# Ampli50g.net
KiCad netlist of a schematic drawn in Altium Designer
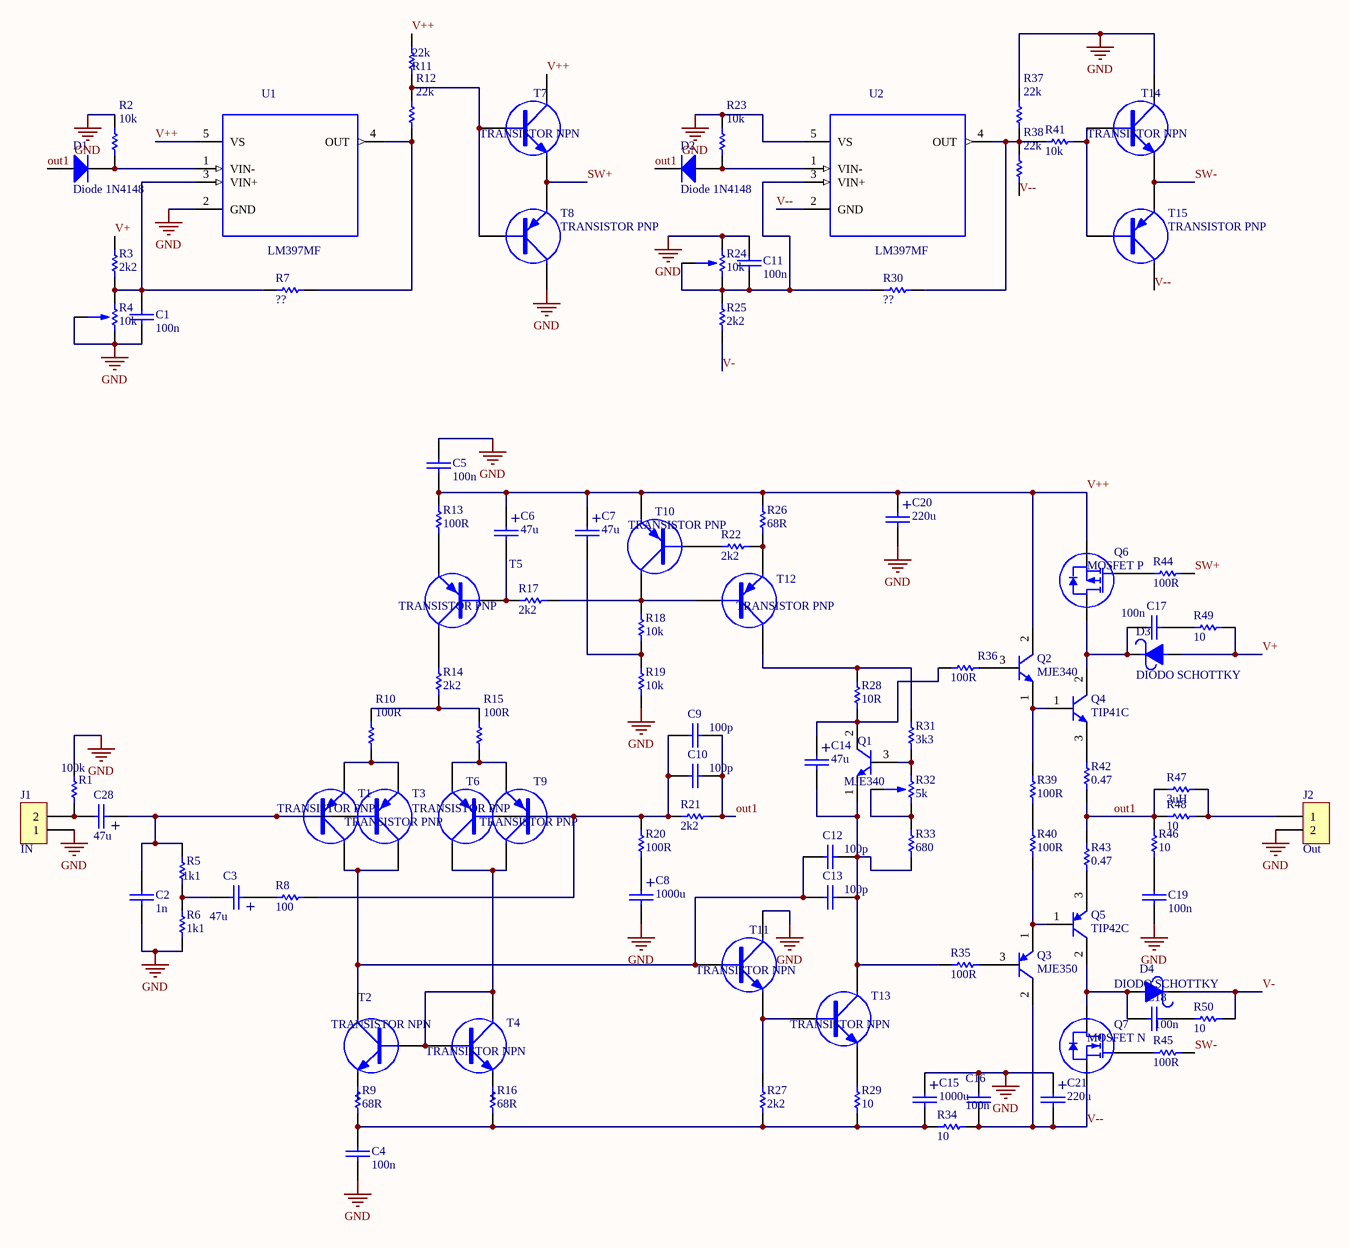
[diagram p0: Ampli50g.SchDoc]

(export (version "E")
  (design (tool "Eeschema 10.0.6"))
  (components
    (comp (ref "C1") (value "100n") (footprint "0805") (libsource (lib "LIBEBAL") (part "CAP")))
    (comp (ref "C2") (value "1n") (footprint "CAP200") (libsource (lib "LIBEBAL") (part "CAP")))
    (comp (ref "C3") (value "47u") (footprint "CAP100RP") (libsource (lib "LIBEBAL") (part "CAPPOL")))
    (comp (ref "C4") (value "100n") (footprint "CAP200") (libsource (lib "LIBEBAL") (part "CAP")))
    (comp (ref "C5") (value "100n") (footprint "CAP200") (libsource (lib "LIBEBAL") (part "CAP")))
    (comp (ref "C6") (value "47u") (footprint "CAP100RP") (libsource (lib "LIBEBAL") (part "CAPPOL")))
    (comp (ref "C7") (value "47u") (footprint "CAP100RP") (libsource (lib "LIBEBAL") (part "CAPPOL")))
    (comp (ref "C8") (value "1000u") (footprint "CAP200RP2") (libsource (lib "LIBEBAL") (part "CAPPOL")))
    (comp (ref "C9") (value "100p") (footprint "0805") (libsource (lib "LIBEBAL") (part "CAP")))
    (comp (ref "C10") (value "100p") (footprint "0805") (libsource (lib "LIBEBAL") (part "CAP")))
    (comp (ref "C11") (value "100n") (footprint "0805") (libsource (lib "LIBEBAL") (part "CAP")))
    (comp (ref "C12") (value "100p") (footprint "0805") (libsource (lib "LIBEBAL") (part "CAP")))
    (comp (ref "C13") (value "100p") (footprint "0805") (libsource (lib "LIBEBAL") (part "CAP")))
    (comp (ref "C14") (value "47u") (footprint "CAP100RP") (libsource (lib "LIBEBAL") (part "CAPPOL")))
    (comp (ref "C15") (value "1000u") (footprint "CAP200RP2") (libsource (lib "LIBEBAL") (part "CAPPOL")))
    (comp (ref "C16") (value "100n") (footprint "CAP200") (libsource (lib "LIBEBAL") (part "CAP")))
    (comp (ref "C17") (value "100n") (footprint "CAP200") (libsource (lib "LIBEBAL") (part "CAP")))
    (comp (ref "C18") (value "100n") (footprint "CAP200") (libsource (lib "LIBEBAL") (part "CAP")))
    (comp (ref "C19") (value "100n") (footprint "CAP200") (libsource (lib "LIBEBAL") (part "CAP")))
    (comp (ref "C20") (value "220u") (footprint "CAP200RP2") (libsource (lib "LIBEBAL") (part "CAPPOL")))
    (comp (ref "C21") (value "220u") (footprint "CAP200RP2") (libsource (lib "LIBEBAL") (part "CAPPOL")))
    (comp (ref "C28") (value "47u") (footprint "CAP100RP") (libsource (lib "LIBEBAL") (part "CAPPOL")))
    (comp (ref "D1")
      (value "Diode 1N4148")
      (footprint "DO-35")
      (description "High Conductance Fast Diode")
      (fields (field (name "PUBLISHER") "Altium Limited"))
      (libsource (lib "Miscellaneous Devices") (part "Diode 1N4148"))
    )
    (comp (ref "D2")
      (value "Diode 1N4148")
      (footprint "DO-35")
      (description "High Conductance Fast Diode")
      (fields (field (name "PUBLISHER") "Altium Limited"))
      (libsource (lib "Miscellaneous Devices") (part "Diode 1N4148"))
    )
    (comp (ref "D3")
      (value "DIODO SCHOTTKY")
      (footprint "SMCK")
      (libsource (lib "LIBEBAL") (part "DIODO SCHOTTKY"))
    )
    (comp (ref "D4")
      (value "DIODO SCHOTTKY")
      (footprint "SMCK")
      (libsource (lib "LIBEBAL") (part "DIODO SCHOTTKY"))
    )
    (comp (ref "J1") (value "IN") (footprint "BORNERA2") (libsource (lib "LIBEBAL") (part "BORNERA 2")))
    (comp (ref "J2") (value "Out") (footprint "BORNERA2") (libsource (lib "") (part "BORNERA 2_1")))
    (comp (ref "Q1")
      (value "MJE340")
      (footprint "ONSC-TO-225-3-77-09")
      (description "Plastic Medium-Power NPN Silicon Transistor, 3-Pin TO-225, Bulk Box")
      (fields (field (name "MANUFACTURER") "On Semiconductor"))
      (libsource (lib "ON Semi General Purpose Transistors") (part "MJE340"))
    )
    (comp (ref "Q2")
      (value "MJE340")
      (footprint "ONSC-TO-225-3-77-09")
      (description "Plastic Medium-Power NPN Silicon Transistor, 3-Pin TO-225, Bulk Box")
      (fields (field (name "MANUFACTURER") "On Semiconductor"))
      (libsource (lib "ON Semi General Purpose Transistors") (part "MJE340"))
    )
    (comp (ref "Q3")
      (value "MJE350")
      (footprint "ONSC-TO-225-3-77-09")
      (description "Plastic Medium-Power PNP Silicon Transistor, 3-Pin TO-225, Bulk Box")
      (fields (field (name "MANUFACTURER") "On Semiconductor"))
      (libsource (lib "ON Semi General Purpose Transistors") (part "MJE350"))
    )
    (comp (ref "Q4")
      (value "TIP41C")
      (footprint "ONSC-TO-220-3-221A-09")
      (description "Complementary Silicon Plastic Power Transistor, 3-Pin TO-220, Tube")
      (fields (field (name "MANUFACTURER") "On Semiconductor"))
      (libsource (lib "ON Semi General Purpose Transistors") (part "TIP41C"))
    )
    (comp (ref "Q5")
      (value "TIP42C")
      (footprint "ONSC-TO-220-3-221A-09")
      (description "Complementary Silicon Plastic Power Transistor, 3-Pin TO-220, Tube")
      (fields (field (name "MANUFACTURER") "On Semiconductor"))
      (libsource (lib "ON Semi General Purpose Transistors") (part "TIP42C"))
    )
    (comp (ref "Q6") (value "MOSFET P") (footprint "TO-220 V") (libsource (lib "LIBEBAL") (part "MOSFET P")))
    (comp (ref "Q7") (value "MOSFET N") (footprint "TO-220 V") (libsource (lib "LIBEBAL") (part "MOSFET N")))
    (comp (ref "R1") (value "100k") (footprint "RES400") (libsource (lib "LIBEBAL") (part "RES")))
    (comp (ref "R2") (value "10k") (footprint "1206") (libsource (lib "LIBEBAL") (part "RES")))
    (comp (ref "R3") (value "2k2") (footprint "RES400") (libsource (lib "LIBEBAL") (part "RES")))
    (comp (ref "R4") (value "10k") (footprint "PRESET V") (libsource (lib "LIBEBAL") (part "PRESET")))
    (comp (ref "R5") (value "1k1") (footprint "1206") (libsource (lib "LIBEBAL") (part "RES")))
    (comp (ref "R6") (value "1k1") (footprint "1206") (libsource (lib "LIBEBAL") (part "RES")))
    (comp (ref "R7")
      (value "??")
      (footprint "1206")
      (description "RES SMD 1/2W 1206")
      (libsource (lib "LIBEBAL") (part "RES"))
    )
    (comp (ref "R8") (value "100") (footprint "1206") (libsource (lib "LIBEBAL") (part "RES")))
    (comp (ref "R9") (value "68R") (footprint "1206") (libsource (lib "LIBEBAL") (part "RES")))
    (comp (ref "R10") (value "100R") (footprint "1206") (libsource (lib "LIBEBAL") (part "RES")))
    (comp (ref "R11")
      (value "22k")
      (footprint "1206")
      (description "RES SMD 1/2W 1206")
      (libsource (lib "LIBEBAL") (part "RES"))
    )
    (comp (ref "R12")
      (value "22k")
      (footprint "1206")
      (description "RES SMD 1/2W 1206")
      (libsource (lib "LIBEBAL") (part "RES"))
    )
    (comp (ref "R13") (value "100R") (footprint "1206") (libsource (lib "LIBEBAL") (part "RES")))
    (comp (ref "R14") (value "2k2") (footprint "1206") (libsource (lib "LIBEBAL") (part "RES")))
    (comp (ref "R15")
      (value "100R")
      (footprint "1206")
      (description "RES SMD 1/2W 1206")
      (libsource (lib "LIBEBAL") (part "RES"))
    )
    (comp (ref "R16") (value "68R") (footprint "1206") (libsource (lib "LIBEBAL") (part "RES")))
    (comp (ref "R17") (value "2k2") (footprint "1206") (libsource (lib "LIBEBAL") (part "RES")))
    (comp (ref "R18") (value "10k") (footprint "1206") (libsource (lib "LIBEBAL") (part "RES")))
    (comp (ref "R19") (value "10k") (footprint "1206") (libsource (lib "LIBEBAL") (part "RES")))
    (comp (ref "R20") (value "100R") (footprint "1206") (libsource (lib "LIBEBAL") (part "RES")))
    (comp (ref "R21") (value "2k2") (footprint "1206") (libsource (lib "LIBEBAL") (part "RES")))
    (comp (ref "R22") (value "2k2") (footprint "1206") (libsource (lib "LIBEBAL") (part "RES")))
    (comp (ref "R23") (value "10k") (footprint "1206") (libsource (lib "LIBEBAL") (part "RES")))
    (comp (ref "R24") (value "10k") (footprint "PRESET V") (libsource (lib "LIBEBAL") (part "PRESET")))
    (comp (ref "R25") (value "2k2") (footprint "RES400") (libsource (lib "LIBEBAL") (part "RES")))
    (comp (ref "R26") (value "68R") (footprint "1206") (libsource (lib "LIBEBAL") (part "RES")))
    (comp (ref "R27") (value "2k2") (footprint "1206") (libsource (lib "LIBEBAL") (part "RES")))
    (comp (ref "R28") (value "10R") (footprint "1206") (libsource (lib "LIBEBAL") (part "RES")))
    (comp (ref "R29") (value "10") (footprint "1206") (libsource (lib "LIBEBAL") (part "RES")))
    (comp (ref "R30")
      (value "??")
      (footprint "1206")
      (description "RES SMD 1/2W 1206")
      (libsource (lib "LIBEBAL") (part "RES"))
    )
    (comp (ref "R31") (value "3k3") (footprint "1206") (libsource (lib "LIBEBAL") (part "RES")))
    (comp (ref "R32") (value "5k") (footprint "PRESET V") (libsource (lib "LIBEBAL") (part "PRESET")))
    (comp (ref "R33") (value "680") (footprint "1206") (libsource (lib "LIBEBAL") (part "RES")))
    (comp (ref "R34") (value "10") (footprint "RES500") (libsource (lib "LIBEBAL") (part "RES")))
    (comp (ref "R35") (value "100R") (footprint "1206") (libsource (lib "LIBEBAL") (part "RES")))
    (comp (ref "R36") (value "100R") (footprint "1206") (libsource (lib "LIBEBAL") (part "RES")))
    (comp (ref "R37")
      (value "22k")
      (footprint "1206")
      (description "RES SMD 1/2W 1206")
      (libsource (lib "LIBEBAL") (part "RES"))
    )
    (comp (ref "R38")
      (value "22k")
      (footprint "1206")
      (description "RES SMD 1/2W 1206")
      (libsource (lib "LIBEBAL") (part "RES"))
    )
    (comp (ref "R39") (value "100R") (footprint "RES500") (libsource (lib "LIBEBAL") (part "RES")))
    (comp (ref "R40") (value "100R") (footprint "RES500") (libsource (lib "LIBEBAL") (part "RES")))
    (comp (ref "R41")
      (value "10k")
      (footprint "1206")
      (description "RES SMD 1/2W 1206")
      (libsource (lib "LIBEBAL") (part "RES"))
    )
    (comp (ref "R42") (value "0.47") (footprint "RES1200") (libsource (lib "LIBEBAL") (part "RES")))
    (comp (ref "R43") (value "0.47") (footprint "RES1200") (libsource (lib "LIBEBAL") (part "RES")))
    (comp (ref "R44") (value "100R") (footprint "1206") (libsource (lib "LIBEBAL") (part "RES")))
    (comp (ref "R45") (value "100R") (footprint "1206") (libsource (lib "LIBEBAL") (part "RES")))
    (comp (ref "R46") (value "10") (footprint "RES600") (libsource (lib "LIBEBAL") (part "RES")))
    (comp (ref "R47") (value "3uH") (footprint "RES600") (libsource (lib "LIBEBAL") (part "RES")))
    (comp (ref "R48") (value "10") (footprint "RES600") (libsource (lib "LIBEBAL") (part "RES")))
    (comp (ref "R49") (value "10") (footprint "1206") (libsource (lib "LIBEBAL") (part "RES")))
    (comp (ref "R50") (value "10") (footprint "1206") (libsource (lib "LIBEBAL") (part "RES")))
    (comp (ref "T1")
      (value "TRANSISTOR PNP")
      (footprint "SOT23")
      (libsource (lib "LIBEBAL") (part "TRANSISTOR PNP"))
    )
    (comp (ref "T2")
      (value "TRANSISTOR NPN")
      (footprint "SOT23")
      (libsource (lib "LIBEBAL") (part "TRANSISTOR NPN"))
    )
    (comp (ref "T3")
      (value "TRANSISTOR PNP")
      (footprint "SOT23")
      (libsource (lib "LIBEBAL") (part "TRANSISTOR PNP"))
    )
    (comp (ref "T4")
      (value "TRANSISTOR NPN")
      (footprint "SOT23")
      (libsource (lib "LIBEBAL") (part "TRANSISTOR NPN"))
    )
    (comp (ref "T5")
      (value "TRANSISTOR PNP")
      (footprint "SOT23")
      (libsource (lib "LIBEBAL") (part "TRANSISTOR PNP"))
    )
    (comp (ref "T6")
      (value "TRANSISTOR PNP")
      (footprint "SOT23")
      (libsource (lib "LIBEBAL") (part "TRANSISTOR PNP"))
    )
    (comp (ref "T7")
      (value "TRANSISTOR NPN")
      (footprint "SOT23")
      (libsource (lib "LIBEBAL") (part "TRANSISTOR NPN"))
    )
    (comp (ref "T8")
      (value "TRANSISTOR PNP")
      (footprint "SOT23")
      (libsource (lib "LIBEBAL") (part "TRANSISTOR PNP"))
    )
    (comp (ref "T9")
      (value "TRANSISTOR PNP")
      (footprint "SOT23")
      (libsource (lib "LIBEBAL") (part "TRANSISTOR PNP"))
    )
    (comp (ref "T10")
      (value "TRANSISTOR PNP")
      (footprint "SOT23")
      (libsource (lib "LIBEBAL") (part "TRANSISTOR PNP"))
    )
    (comp (ref "T11")
      (value "TRANSISTOR NPN")
      (footprint "SOT23")
      (libsource (lib "LIBEBAL") (part "TRANSISTOR NPN"))
    )
    (comp (ref "T12")
      (value "TRANSISTOR PNP")
      (footprint "SOT23")
      (libsource (lib "LIBEBAL") (part "TRANSISTOR PNP"))
    )
    (comp (ref "T13")
      (value "TRANSISTOR NPN")
      (footprint "SOT23")
      (libsource (lib "LIBEBAL") (part "TRANSISTOR NPN"))
    )
    (comp (ref "T14")
      (value "TRANSISTOR NPN")
      (footprint "SOT23")
      (libsource (lib "LIBEBAL") (part "TRANSISTOR NPN"))
    )
    (comp (ref "T15")
      (value "TRANSISTOR PNP")
      (footprint "SOT23")
      (libsource (lib "LIBEBAL") (part "TRANSISTOR PNP"))
    )
    (comp (ref "U1")
      (value "LM397MF")
      (footprint "SOT95P285X120-5N")
      (description "General Purpose Comparator, Single, 250ns, Sot23-5, Full Reel")
      (fields (field (name "MP") "LM397MF/NOPB") (field (name "MF") "Texas Instruments"))
      (libsource (lib "LM397MF") (part "LM397MF"))
    )
    (comp (ref "U2")
      (value "LM397MF")
      (footprint "SOT95P285X120-5N")
      (description "General Purpose Comparator, Single, 250ns, Sot23-5, Full Reel")
      (fields (field (name "MP") "LM397MF/NOPB") (field (name "MF") "Texas Instruments"))
      (libsource (lib "LM397MF") (part "LM397MF"))
    )
  )
  (nets
    (net (code "1") (name "/SW+") (class "Default")
      (node (ref "R44") (pin "1") (pinfunction "1_1") (pintype "passive"))
      (node (ref "T7") (pin "3") (pinfunction "E_3") (pintype "passive"))
      (node (ref "T8") (pin "3") (pinfunction "E_3") (pintype "passive"))
    )
    (net (code "2") (name "/SW-") (class "Default")
      (node (ref "R45") (pin "1") (pinfunction "1_1") (pintype "passive"))
      (node (ref "T14") (pin "3") (pinfunction "E_3") (pintype "passive"))
      (node (ref "T15") (pin "3") (pinfunction "E_3") (pintype "passive"))
    )
    (net (code "3") (name "/V+") (class "Default")
      (node (ref "D3") (pin "1") (pinfunction "1_1") (pintype "passive"))
      (node (ref "R3") (pin "2") (pinfunction "2_2") (pintype "passive"))
      (node (ref "R49") (pin "2") (pinfunction "2_2") (pintype "passive"))
    )
    (net (code "4") (name "/V++") (class "Default")
      (node (ref "C20") (pin "1") (pinfunction "1_1") (pintype "passive"))
      (node (ref "C5") (pin "2") (pinfunction "2_2") (pintype "passive"))
      (node (ref "C6") (pin "1") (pinfunction "1_1") (pintype "passive"))
      (node (ref "C7") (pin "1") (pinfunction "1_1") (pintype "passive"))
      (node (ref "Q2") (pin "2") (pinfunction "C_2") (pintype "passive"))
      (node (ref "Q6") (pin "3") (pinfunction "S_3") (pintype "passive"))
      (node (ref "R11") (pin "2") (pinfunction "2_2") (pintype "passive"))
      (node (ref "R13") (pin "2") (pinfunction "2_2") (pintype "passive"))
      (node (ref "R26") (pin "2") (pinfunction "2_2") (pintype "passive"))
      (node (ref "T10") (pin "3") (pinfunction "E_3") (pintype "passive"))
      (node (ref "T7") (pin "2") (pinfunction "C_2") (pintype "passive"))
      (node (ref "U1") (pin "5") (pinfunction "VS_5") (pintype "power_in"))
    )
    (net (code "5") (name "/V-") (class "Default")
      (node (ref "D4") (pin "2") (pinfunction "2_2") (pintype "passive"))
      (node (ref "R25") (pin "1") (pinfunction "1_1") (pintype "passive"))
      (node (ref "R50") (pin "2") (pinfunction "2_2") (pintype "passive"))
    )
    (net (code "6") (name "/V--") (class "Default")
      (node (ref "C16") (pin "2") (pinfunction "2_2") (pintype "passive"))
      (node (ref "C21") (pin "2") (pinfunction "2_2") (pintype "passive"))
      (node (ref "Q3") (pin "2") (pinfunction "C_2") (pintype "passive"))
      (node (ref "Q7") (pin "3") (pinfunction "S_3") (pintype "passive"))
      (node (ref "R34") (pin "1") (pinfunction "1_1") (pintype "passive"))
      (node (ref "R38") (pin "1") (pinfunction "1_1") (pintype "passive"))
      (node (ref "T15") (pin "2") (pinfunction "C_2") (pintype "passive"))
      (node (ref "U2") (pin "2") (pinfunction "GND_2") (pintype "passive"))
    )
    (net (code "7") (name "/out1") (class "Default")
      (node (ref "C10") (pin "2") (pinfunction "2_2") (pintype "passive"))
      (node (ref "C9") (pin "2") (pinfunction "2_2") (pintype "passive"))
      (node (ref "D1") (pin "1") (pinfunction "A_1") (pintype "passive"))
      (node (ref "D2") (pin "2") (pinfunction "K_2") (pintype "passive"))
      (node (ref "R21") (pin "1") (pinfunction "1_1") (pintype "passive"))
      (node (ref "R42") (pin "1") (pinfunction "1_1") (pintype "passive"))
      (node (ref "R43") (pin "2") (pinfunction "2_2") (pintype "passive"))
      (node (ref "R46") (pin "2") (pinfunction "2_2") (pintype "passive"))
      (node (ref "R47") (pin "2") (pinfunction "2_2") (pintype "passive"))
      (node (ref "R48") (pin "2") (pinfunction "2_2") (pintype "passive"))
    )
    (net (code "8") (name "GND") (class "Default")
      (node (ref "C1") (pin "1") (pinfunction "1_1") (pintype "passive"))
      (node (ref "C11") (pin "2") (pinfunction "2_2") (pintype "passive"))
      (node (ref "C15") (pin "1") (pinfunction "1_1") (pintype "passive"))
      (node (ref "C16") (pin "1") (pinfunction "1_1") (pintype "passive"))
      (node (ref "C19") (pin "2") (pinfunction "2_2") (pintype "passive"))
      (node (ref "C2") (pin "2") (pinfunction "2_2") (pintype "passive"))
      (node (ref "C20") (pin "2") (pinfunction "2_2") (pintype "passive"))
      (node (ref "C21") (pin "1") (pinfunction "1_1") (pintype "passive"))
      (node (ref "C4") (pin "2") (pinfunction "2_2") (pintype "passive"))
      (node (ref "C5") (pin "1") (pinfunction "1_1") (pintype "passive"))
      (node (ref "C8") (pin "2") (pinfunction "2_2") (pintype "passive"))
      (node (ref "J1") (pin "1") (pinfunction "1_1") (pintype "passive"))
      (node (ref "J2") (pin "2") (pinfunction "2_2") (pintype "passive"))
      (node (ref "R1") (pin "2") (pinfunction "2_2") (pintype "passive"))
      (node (ref "R19") (pin "2") (pinfunction "2_2") (pintype "passive"))
      (node (ref "R2") (pin "2") (pinfunction "2_2") (pintype "passive"))
      (node (ref "R23") (pin "2") (pinfunction "2_2") (pintype "passive"))
      (node (ref "R24") (pin "3") (pinfunction "3_3") (pintype "passive"))
      (node (ref "R37") (pin "2") (pinfunction "2_2") (pintype "passive"))
      (node (ref "R4") (pin "1") (pinfunction "1_1") (pintype "passive"))
      (node (ref "R4") (pin "2") (pinfunction "2_2") (pintype "passive"))
      (node (ref "R6") (pin "1") (pinfunction "1_1") (pintype "passive"))
      (node (ref "T11") (pin "2") (pinfunction "C_2") (pintype "passive"))
      (node (ref "T14") (pin "2") (pinfunction "C_2") (pintype "passive"))
      (node (ref "T8") (pin "2") (pinfunction "C_2") (pintype "passive"))
      (node (ref "U1") (pin "2") (pinfunction "GND_2") (pintype "passive"))
      (node (ref "U2") (pin "5") (pinfunction "VS_5") (pintype "power_in"))
    )
    (net (code "9") (name "Net-(C3-Pad1)") (class "Default")
      (node (ref "C3") (pin "1") (pinfunction "1_1") (pintype "passive"))
      (node (ref "R8") (pin "2") (pinfunction "2_2") (pintype "passive"))
    )
    (net (code "10") (name "Net-(C3-Pad2)") (class "Default")
      (node (ref "C3") (pin "2") (pinfunction "2_2") (pintype "passive"))
      (node (ref "R5") (pin "1") (pinfunction "1_1") (pintype "passive"))
      (node (ref "R6") (pin "2") (pinfunction "2_2") (pintype "passive"))
    )
    (net (code "11") (name "Net-(C7-Pad2)") (class "Default")
      (node (ref "C7") (pin "2") (pinfunction "2_2") (pintype "passive"))
      (node (ref "R18") (pin "2") (pinfunction "2_2") (pintype "passive"))
      (node (ref "R19") (pin "1") (pinfunction "1_1") (pintype "passive"))
    )
    (net (code "12") (name "Net-(C8-Pad1)") (class "Default")
      (node (ref "C8") (pin "1") (pinfunction "1_1") (pintype "passive"))
      (node (ref "R20") (pin "1") (pinfunction "1_1") (pintype "passive"))
    )
    (net (code "13") (name "Net-(C15-Pad2)") (class "Default")
      (node (ref "C15") (pin "2") (pinfunction "2_2") (pintype "passive"))
      (node (ref "C4") (pin "1") (pinfunction "1_1") (pintype "passive"))
      (node (ref "R16") (pin "1") (pinfunction "1_1") (pintype "passive"))
      (node (ref "R27") (pin "2") (pinfunction "2_2") (pintype "passive"))
      (node (ref "R29") (pin "2") (pinfunction "2_2") (pintype "passive"))
      (node (ref "R34") (pin "2") (pinfunction "2_2") (pintype "passive"))
      (node (ref "R9") (pin "1") (pinfunction "1_1") (pintype "passive"))
    )
    (net (code "14") (name "Net-(C17-Pad2)") (class "Default")
      (node (ref "C17") (pin "2") (pinfunction "2_2") (pintype "passive"))
      (node (ref "R49") (pin "1") (pinfunction "1_1") (pintype "passive"))
    )
    (net (code "15") (name "Net-(C18-Pad2)") (class "Default")
      (node (ref "C18") (pin "2") (pinfunction "2_2") (pintype "passive"))
      (node (ref "R50") (pin "1") (pinfunction "1_1") (pintype "passive"))
    )
    (net (code "16") (name "Net-(C19-Pad1)") (class "Default")
      (node (ref "C19") (pin "1") (pinfunction "1_1") (pintype "passive"))
      (node (ref "R46") (pin "1") (pinfunction "1_1") (pintype "passive"))
    )
    (net (code "17") (name "Net-(C28-Pad2)") (class "Default")
      (node (ref "C28") (pin "2") (pinfunction "2_2") (pintype "passive"))
      (node (ref "J1") (pin "2") (pinfunction "2_2") (pintype "passive"))
      (node (ref "R1") (pin "1") (pinfunction "1_1") (pintype "passive"))
    )
    (net (code "18") (name "Net-(D1-K)") (class "Default")
      (node (ref "D1") (pin "2") (pinfunction "K_2") (pintype "passive"))
      (node (ref "R2") (pin "1") (pinfunction "1_1") (pintype "passive"))
      (node (ref "U1") (pin "1") (pinfunction "VIN-_1") (pintype "input"))
    )
    (net (code "19") (name "Net-(D2-A)") (class "Default")
      (node (ref "D2") (pin "1") (pinfunction "A_1") (pintype "passive"))
      (node (ref "R23") (pin "1") (pinfunction "1_1") (pintype "passive"))
      (node (ref "U2") (pin "1") (pinfunction "VIN-_1") (pintype "input"))
    )
    (net (code "20") (name "Net-(J2-Pad1)") (class "Default")
      (node (ref "J2") (pin "1") (pinfunction "1_1") (pintype "passive"))
      (node (ref "R47") (pin "1") (pinfunction "1_1") (pintype "passive"))
      (node (ref "R48") (pin "1") (pinfunction "1_1") (pintype "passive"))
    )
    (net (code "21") (name "Net-(Q1-B)") (class "Default")
      (node (ref "Q1") (pin "3") (pinfunction "B_3") (pintype "passive"))
      (node (ref "R31") (pin "1") (pinfunction "1_1") (pintype "passive"))
      (node (ref "R32") (pin "3") (pinfunction "3_3") (pintype "passive"))
    )
    (net (code "22") (name "Net-(Q1-C)") (class "Default")
      (node (ref "C14") (pin "1") (pinfunction "1_1") (pintype "passive"))
      (node (ref "Q1") (pin "2") (pinfunction "C_2") (pintype "passive"))
      (node (ref "R28") (pin "1") (pinfunction "1_1") (pintype "passive"))
      (node (ref "R36") (pin "2") (pinfunction "2_2") (pintype "passive"))
    )
    (net (code "23") (name "Net-(Q1-E)") (class "Default")
      (node (ref "C12") (pin "2") (pinfunction "2_2") (pintype "passive"))
      (node (ref "C13") (pin "2") (pinfunction "2_2") (pintype "passive"))
      (node (ref "C14") (pin "2") (pinfunction "2_2") (pintype "passive"))
      (node (ref "Q1") (pin "1") (pinfunction "E_1") (pintype "passive"))
      (node (ref "R33") (pin "1") (pinfunction "1_1") (pintype "passive"))
      (node (ref "R35") (pin "2") (pinfunction "2_2") (pintype "passive"))
      (node (ref "T13") (pin "2") (pinfunction "C_2") (pintype "passive"))
    )
    (net (code "24") (name "Net-(Q2-B)") (class "Default")
      (node (ref "Q2") (pin "3") (pinfunction "B_3") (pintype "passive"))
      (node (ref "R36") (pin "1") (pinfunction "1_1") (pintype "passive"))
    )
    (net (code "25") (name "Net-(Q2-E)") (class "Default")
      (node (ref "Q2") (pin "1") (pinfunction "E_1") (pintype "passive"))
      (node (ref "Q4") (pin "1") (pinfunction "B_1") (pintype "passive"))
      (node (ref "R39") (pin "2") (pinfunction "2_2") (pintype "passive"))
    )
    (net (code "26") (name "Net-(Q3-B)") (class "Default")
      (node (ref "Q3") (pin "3") (pinfunction "B_3") (pintype "passive"))
      (node (ref "R35") (pin "1") (pinfunction "1_1") (pintype "passive"))
    )
    (net (code "27") (name "Net-(Q3-E)") (class "Default")
      (node (ref "Q3") (pin "1") (pinfunction "E_1") (pintype "passive"))
      (node (ref "Q5") (pin "1") (pinfunction "B_1") (pintype "passive"))
      (node (ref "R40") (pin "1") (pinfunction "1_1") (pintype "passive"))
    )
    (net (code "28") (name "Net-(Q4-C)") (class "Default")
      (node (ref "C17") (pin "1") (pinfunction "1_1") (pintype "passive"))
      (node (ref "D3") (pin "2") (pinfunction "2_2") (pintype "passive"))
      (node (ref "Q4") (pin "2") (pinfunction "C_2") (pintype "passive"))
      (node (ref "Q6") (pin "2") (pinfunction "D_2") (pintype "passive"))
    )
    (net (code "29") (name "Net-(Q4-E)") (class "Default")
      (node (ref "Q4") (pin "3") (pinfunction "E_3") (pintype "passive"))
      (node (ref "R42") (pin "2") (pinfunction "2_2") (pintype "passive"))
    )
    (net (code "30") (name "Net-(Q5-C)") (class "Default")
      (node (ref "C18") (pin "1") (pinfunction "1_1") (pintype "passive"))
      (node (ref "D4") (pin "1") (pinfunction "1_1") (pintype "passive"))
      (node (ref "Q5") (pin "2") (pinfunction "C_2") (pintype "passive"))
      (node (ref "Q7") (pin "2") (pinfunction "D_2") (pintype "passive"))
    )
    (net (code "31") (name "Net-(Q5-E)") (class "Default")
      (node (ref "Q5") (pin "3") (pinfunction "E_3") (pintype "passive"))
      (node (ref "R43") (pin "1") (pinfunction "1_1") (pintype "passive"))
    )
    (net (code "32") (name "Net-(Q6-G)") (class "Default")
      (node (ref "Q6") (pin "1") (pinfunction "G_1") (pintype "passive"))
      (node (ref "R44") (pin "2") (pinfunction "2_2") (pintype "passive"))
    )
    (net (code "33") (name "Net-(Q7-G)") (class "Default")
      (node (ref "Q7") (pin "1") (pinfunction "G_1") (pintype "passive"))
      (node (ref "R45") (pin "2") (pinfunction "2_2") (pintype "passive"))
    )
    (net (code "34") (name "Net-(R10-Pad2)") (class "Default")
      (node (ref "R10") (pin "2") (pinfunction "2_2") (pintype "passive"))
      (node (ref "R14") (pin "2") (pinfunction "2_2") (pintype "passive"))
      (node (ref "R15") (pin "2") (pinfunction "2_2") (pintype "passive"))
    )
    (net (code "35") (name "Net-(R32-Pad1)") (class "Default")
      (node (ref "R32") (pin "1") (pinfunction "1_1") (pintype "passive"))
      (node (ref "R32") (pin "2") (pinfunction "2_2") (pintype "passive"))
      (node (ref "R33") (pin "2") (pinfunction "2_2") (pintype "passive"))
    )
    (net (code "36") (name "Net-(R39-Pad1)") (class "Default")
      (node (ref "R39") (pin "1") (pinfunction "1_1") (pintype "passive"))
      (node (ref "R40") (pin "2") (pinfunction "2_2") (pintype "passive"))
    )
    (net (code "37") (name "Net-(T1-B)") (class "Default")
      (node (ref "C2") (pin "1") (pinfunction "1_1") (pintype "passive"))
      (node (ref "C28") (pin "1") (pinfunction "1_1") (pintype "passive"))
      (node (ref "R5") (pin "2") (pinfunction "2_2") (pintype "passive"))
      (node (ref "T1") (pin "1") (pinfunction "B_1") (pintype "passive"))
      (node (ref "T3") (pin "1") (pinfunction "B_1") (pintype "passive"))
    )
    (net (code "38") (name "Net-(T1-C)") (class "Default")
      (node (ref "C12") (pin "1") (pinfunction "1_1") (pintype "passive"))
      (node (ref "C13") (pin "1") (pinfunction "1_1") (pintype "passive"))
      (node (ref "T1") (pin "2") (pinfunction "C_2") (pintype "passive"))
      (node (ref "T11") (pin "1") (pinfunction "B_1") (pintype "passive"))
      (node (ref "T2") (pin "2") (pinfunction "C_2") (pintype "passive"))
      (node (ref "T3") (pin "2") (pinfunction "C_2") (pintype "passive"))
    )
    (net (code "39") (name "Net-(T1-E)") (class "Default")
      (node (ref "R10") (pin "1") (pinfunction "1_1") (pintype "passive"))
      (node (ref "T1") (pin "3") (pinfunction "E_3") (pintype "passive"))
      (node (ref "T3") (pin "3") (pinfunction "E_3") (pintype "passive"))
    )
    (net (code "40") (name "Net-(T2-B)") (class "Default")
      (node (ref "T2") (pin "1") (pinfunction "B_1") (pintype "passive"))
      (node (ref "T4") (pin "1") (pinfunction "B_1") (pintype "passive"))
      (node (ref "T4") (pin "2") (pinfunction "C_2") (pintype "passive"))
      (node (ref "T6") (pin "2") (pinfunction "C_2") (pintype "passive"))
      (node (ref "T9") (pin "2") (pinfunction "C_2") (pintype "passive"))
    )
    (net (code "41") (name "Net-(T5-B)") (class "Default")
      (node (ref "C6") (pin "2") (pinfunction "2_2") (pintype "passive"))
      (node (ref "R17") (pin "2") (pinfunction "2_2") (pintype "passive"))
      (node (ref "T5") (pin "1") (pinfunction "B_1") (pintype "passive"))
    )
    (net (code "42") (name "Net-(T5-C)") (class "Default")
      (node (ref "R14") (pin "1") (pinfunction "1_1") (pintype "passive"))
      (node (ref "T5") (pin "2") (pinfunction "C_2") (pintype "passive"))
    )
    (net (code "43") (name "Net-(T5-E)") (class "Default")
      (node (ref "R13") (pin "1") (pinfunction "1_1") (pintype "passive"))
      (node (ref "T5") (pin "3") (pinfunction "E_3") (pintype "passive"))
    )
    (net (code "44") (name "Net-(T6-B)") (class "Default")
      (node (ref "C10") (pin "1") (pinfunction "1_1") (pintype "passive"))
      (node (ref "C9") (pin "1") (pinfunction "1_1") (pintype "passive"))
      (node (ref "R20") (pin "2") (pinfunction "2_2") (pintype "passive"))
      (node (ref "R21") (pin "2") (pinfunction "2_2") (pintype "passive"))
      (node (ref "R8") (pin "1") (pinfunction "1_1") (pintype "passive"))
      (node (ref "T6") (pin "1") (pinfunction "B_1") (pintype "passive"))
      (node (ref "T9") (pin "1") (pinfunction "B_1") (pintype "passive"))
    )
    (net (code "45") (name "Net-(T6-E)") (class "Default")
      (node (ref "R15") (pin "1") (pinfunction "1_1") (pintype "passive"))
      (node (ref "T6") (pin "3") (pinfunction "E_3") (pintype "passive"))
      (node (ref "T9") (pin "3") (pinfunction "E_3") (pintype "passive"))
    )
    (net (code "46") (name "Net-(T7-B)") (class "Default")
      (node (ref "R11") (pin "1") (pinfunction "1_1") (pintype "passive"))
      (node (ref "R12") (pin "2") (pinfunction "2_2") (pintype "passive"))
      (node (ref "T7") (pin "1") (pinfunction "B_1") (pintype "passive"))
      (node (ref "T8") (pin "1") (pinfunction "B_1") (pintype "passive"))
    )
    (net (code "47") (name "Net-(T10-B)") (class "Default")
      (node (ref "R22") (pin "2") (pinfunction "2_2") (pintype "passive"))
      (node (ref "T10") (pin "1") (pinfunction "B_1") (pintype "passive"))
    )
    (net (code "48") (name "Net-(T10-C)") (class "Default")
      (node (ref "R17") (pin "1") (pinfunction "1_1") (pintype "passive"))
      (node (ref "R18") (pin "1") (pinfunction "1_1") (pintype "passive"))
      (node (ref "T10") (pin "2") (pinfunction "C_2") (pintype "passive"))
      (node (ref "T12") (pin "1") (pinfunction "B_1") (pintype "passive"))
    )
    (net (code "49") (name "Net-(T11-E)") (class "Default")
      (node (ref "R27") (pin "1") (pinfunction "1_1") (pintype "passive"))
      (node (ref "T11") (pin "3") (pinfunction "E_3") (pintype "passive"))
      (node (ref "T13") (pin "1") (pinfunction "B_1") (pintype "passive"))
    )
    (net (code "50") (name "Net-(T12-C)") (class "Default")
      (node (ref "R28") (pin "2") (pinfunction "2_2") (pintype "passive"))
      (node (ref "R31") (pin "2") (pinfunction "2_2") (pintype "passive"))
      (node (ref "T12") (pin "2") (pinfunction "C_2") (pintype "passive"))
    )
    (net (code "51") (name "Net-(T12-E)") (class "Default")
      (node (ref "R22") (pin "1") (pinfunction "1_1") (pintype "passive"))
      (node (ref "R26") (pin "1") (pinfunction "1_1") (pintype "passive"))
      (node (ref "T12") (pin "3") (pinfunction "E_3") (pintype "passive"))
    )
    (net (code "52") (name "Net-(T13-E)") (class "Default")
      (node (ref "R29") (pin "1") (pinfunction "1_1") (pintype "passive"))
      (node (ref "T13") (pin "3") (pinfunction "E_3") (pintype "passive"))
    )
    (net (code "53") (name "Net-(T14-B)") (class "Default")
      (node (ref "R41") (pin "1") (pinfunction "1_1") (pintype "passive"))
      (node (ref "T14") (pin "1") (pinfunction "B_1") (pintype "passive"))
      (node (ref "T15") (pin "1") (pinfunction "B_1") (pintype "passive"))
    )
    (net (code "54") (name "Net-(U1-OUT)") (class "Default")
      (node (ref "R12") (pin "1") (pinfunction "1_1") (pintype "passive"))
      (node (ref "R7") (pin "1") (pinfunction "1_1") (pintype "passive"))
      (node (ref "U1") (pin "4") (pinfunction "OUT_4") (pintype "output"))
    )
    (net (code "55") (name "Net-(U1-VIN+)") (class "Default")
      (node (ref "C1") (pin "2") (pinfunction "2_2") (pintype "passive"))
      (node (ref "R3") (pin "1") (pinfunction "1_1") (pintype "passive"))
      (node (ref "R4") (pin "3") (pinfunction "3_3") (pintype "passive"))
      (node (ref "R7") (pin "2") (pinfunction "2_2") (pintype "passive"))
      (node (ref "U1") (pin "3") (pinfunction "VIN+_3") (pintype "input"))
    )
    (net (code "56") (name "Net-(U2-OUT)") (class "Default")
      (node (ref "R30") (pin "1") (pinfunction "1_1") (pintype "passive"))
      (node (ref "R37") (pin "1") (pinfunction "1_1") (pintype "passive"))
      (node (ref "R38") (pin "2") (pinfunction "2_2") (pintype "passive"))
      (node (ref "R41") (pin "2") (pinfunction "2_2") (pintype "passive"))
      (node (ref "U2") (pin "4") (pinfunction "OUT_4") (pintype "output"))
    )
    (net (code "57") (name "Net-(U2-VIN+)") (class "Default")
      (node (ref "C11") (pin "1") (pinfunction "1_1") (pintype "passive"))
      (node (ref "R24") (pin "1") (pinfunction "1_1") (pintype "passive"))
      (node (ref "R24") (pin "2") (pinfunction "2_2") (pintype "passive"))
      (node (ref "R25") (pin "2") (pinfunction "2_2") (pintype "passive"))
      (node (ref "R30") (pin "2") (pinfunction "2_2") (pintype "passive"))
      (node (ref "U2") (pin "3") (pinfunction "VIN+_3") (pintype "input"))
    )
    (net (code "58") (name "unconnected-(R9-Pad2)") (class "Default")
      (node (ref "R9") (pin "2") (pinfunction "2_2") (pintype "passive"))
    )
    (net (code "59") (name "unconnected-(R16-Pad2)") (class "Default")
      (node (ref "R16") (pin "2") (pinfunction "2_2") (pintype "passive"))
    )
    (net (code "60") (name "unconnected-(T2-E-Pad3)") (class "Default")
      (node (ref "T2") (pin "3") (pinfunction "E_3") (pintype "passive"))
    )
    (net (code "61") (name "unconnected-(T4-E-Pad3)") (class "Default")
      (node (ref "T4") (pin "3") (pinfunction "E_3") (pintype "passive"))
    )
  )
)
